# OpenRing_Debug.net
KiCad netlist of a schematic drawn in Altium Designer
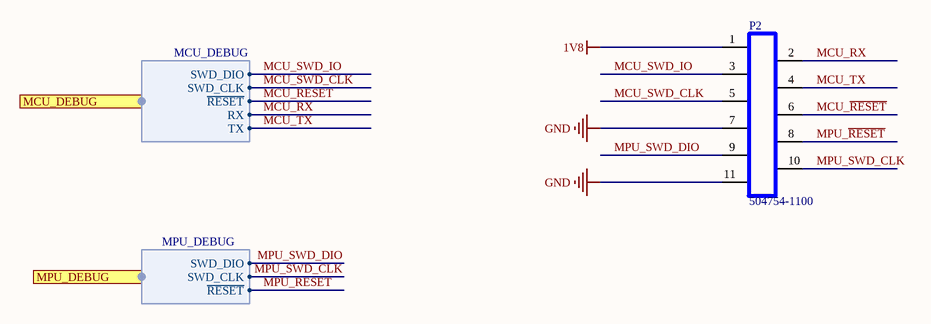
[diagram p0: OpenRing_Debug.SchDoc]

(export (version "E")
  (design (tool "Eeschema 10.0.6"))
  (components
    (comp (ref "P2")
      (value "504754-1100")
      (footprint "5047541100")
      (description "Conn FFC/FPC Connector SKT 11 POS 0.3mm Solder RA SMD Easy-On™ T/R")
      (fields (field (name "MANUFACTURER") "Molex") (field (name "CHECKED") "FALSE"))
      (libsource (lib "Connectors") (part "504754-1100"))
    )
  )
  (nets
    (net (code "3") (name "/MCU_RX") (class "Default")
      (node (ref "P2") (pin "2") (pinfunction "2_2") (pintype "passive"))
    )
    (net (code "4") (name "/MCU_SWD_CLK") (class "Default")
      (node (ref "P2") (pin "5") (pinfunction "5_5") (pintype "passive"))
    )
    (net (code "5") (name "/MCU_SWD_IO") (class "Default")
      (node (ref "P2") (pin "3") (pinfunction "3_3") (pintype "passive"))
    )
    (net (code "6") (name "/MCU_TX") (class "Default")
      (node (ref "P2") (pin "4") (pinfunction "4_4") (pintype "passive"))
    )
    (net (code "7") (name "/MCU_~{RESET}") (class "Default")
      (node (ref "P2") (pin "6") (pinfunction "6_6") (pintype "passive"))
    )
    (net (code "8") (name "/MPU_SWD_CLK") (class "Default")
      (node (ref "P2") (pin "10") (pinfunction "10_10") (pintype "passive"))
    )
    (net (code "9") (name "/MPU_SWD_DIO") (class "Default")
      (node (ref "P2") (pin "9") (pinfunction "9_9") (pintype "passive"))
    )
    (net (code "10") (name "/MPU_~{RESET}") (class "Default")
      (node (ref "P2") (pin "8") (pinfunction "8_8") (pintype "passive"))
    )
    (net (code "13") (name "1V8") (class "Default")
      (node (ref "P2") (pin "1") (pinfunction "1_1") (pintype "passive"))
    )
    (net (code "14") (name "GND") (class "Default")
      (node (ref "P2") (pin "11") (pinfunction "11_11") (pintype "passive"))
      (node (ref "P2") (pin "7") (pinfunction "7_7") (pintype "passive"))
    )
  )
)
